# 09-multimodal-microcontroller-rf.net
KiCad netlist of a schematic drawn in Altium Designer
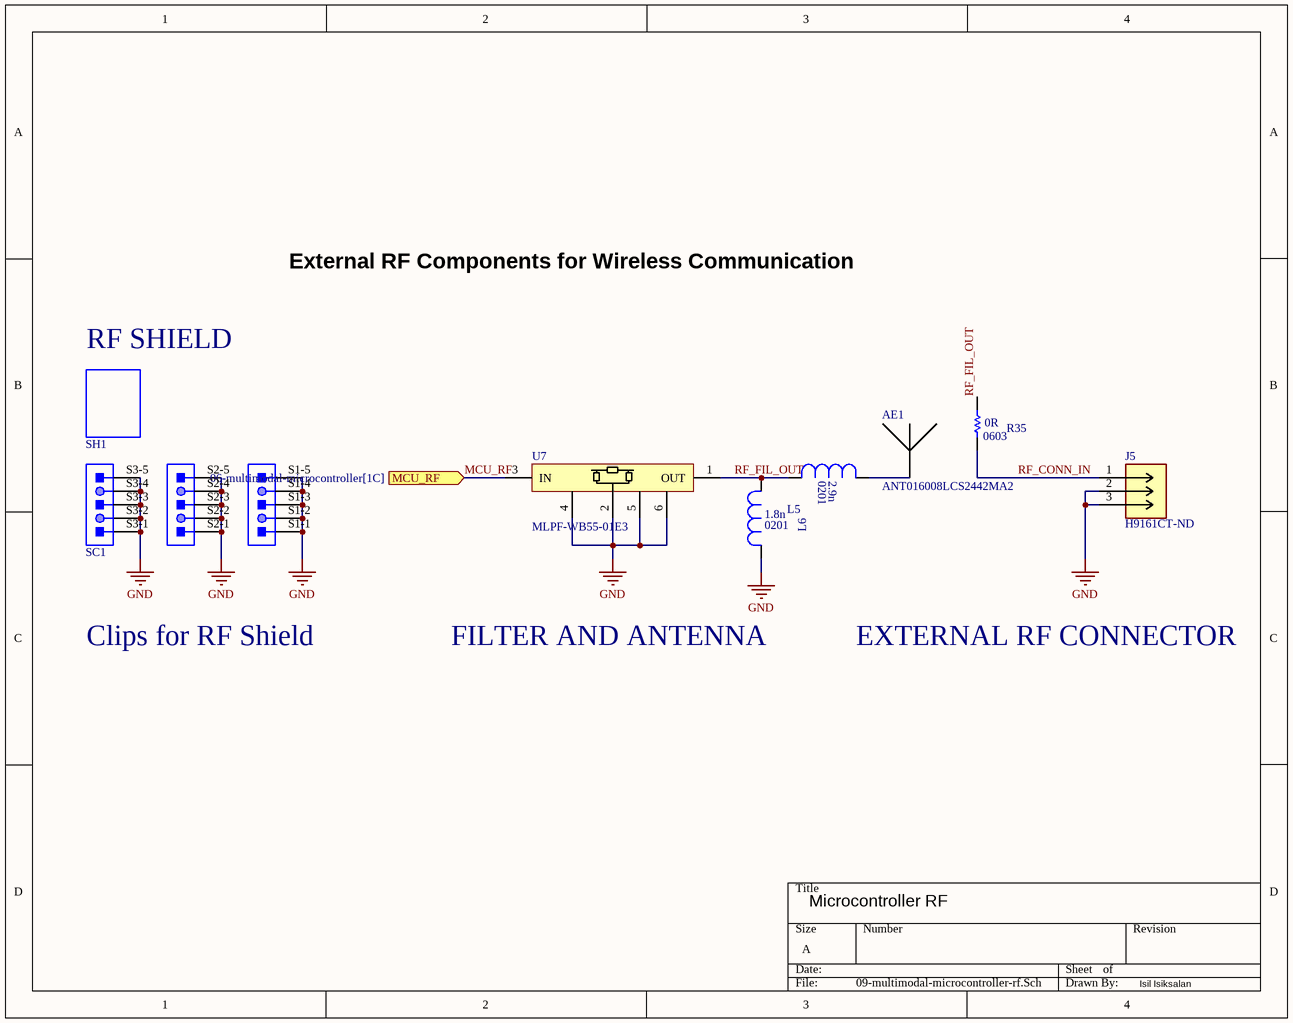
[diagram p0: 09-multimodal-microcontroller-rf.SchDoc]

(export (version "E")
  (design (tool "Eeschema 10.0.6"))
  (components
    (comp (ref "AE1")
      (value "ANT016008LCS2442MA2")
      (footprint "ANTENNA")
      (description "TDK - ANT016008LCS2442MA2 - Chip Antenna, ISM, 2.442 GHz, 50 Ohm, 1.6mm x 0.8mm x 0.4mm")
      (fields (field (name "MANUFACTURER") "TDK"))
      (libsource (lib "multimodal") (part "ANT016008LCS2442MA2"))
    )
    (comp (ref "J5")
      (value "U.FL-R-SMT(10)")
      (footprint "RF-CONNECTOR")
      (description "CONN U.FL RCPT STR 50 OHM SMD")
      (fields
        (field (name "MANUFACTURER") "Hirose")
        (field (name "SUPPLIER PART NUMBER 1") "H9161CT-ND")
        (field (name "COPYRIGHT") "Copyright (C) 2021 Ultra Librarian. All rights reserved.")
      )
      (libsource (lib "multimodal") (part "U.FL-R-SMT(10)"))
    )
    (comp (ref "L5")
      (value "MLG0603P1N8CT000")
      (footprint "INDTDK0201")
      (description "FIXED IND 1.8NH 700MA 100MOHM SM")
      (libsource (lib "multimodal") (part "MLG0603P1N8CT000"))
    )
    (comp (ref "L6")
      (value "MHQ0603P2N9ST000")
      (footprint "INDTDK0201")
      (description "FIXED IND 2.9NH 450MA 300MOHM SM")
      (libsource (lib "multimodal") (part "MHQ0603P2N9ST000"))
    )
    (comp (ref "R35")
      (value "RMCF0603ZT0R00")
      (footprint "RES-STACK-POLE-0603")
      (description "RES 0 OHM JUMPER 1/10W 0603")
      (libsource (lib "multimodal") (part "RMCF0603ZT0R00"))
    )
    (comp (ref "SC1")
      (value "S0951-46R")
      (footprint "RF-SHIELD+CLIP")
      (description "RFI SHIELD CLIP MINI TIN SMD")
      (libsource (lib "multimodal") (part "S0951-46R"))
    )
    (comp (ref "SH1")
      (value "MS190-10C")
      (description "RF SHLD COVER 0.563\"X0.764\" SNAP")
      (libsource (lib "multimodal") (part "MS190-10C"))
    )
    (comp (ref "U7")
      (value "MLPF-WB55-01E3")
      (footprint "Matched-Filter-2.4GHz")
      (description "2.4 GHz Matched filter companion chip for STM32WB55Cx and STM32WB55Rx")
      (fields (field (name "MANUFACTURER") "STMicroelectronics"))
      (libsource (lib "multimodal") (part "MLPF-WB55-01E3"))
    )
  )
  (nets
    (net (code "1") (name "/MCU_RF") (class "Default")
      (node (ref "U7") (pin "3") (pinfunction "IN_3") (pintype "passive"))
    )
    (net (code "2") (name "/RF_CONN_IN") (class "Default")
      (node (ref "J5") (pin "1") (pinfunction "1_1") (pintype "passive"))
      (node (ref "R35") (pin "1") (pinfunction "1_1") (pintype "passive"))
    )
    (net (code "3") (name "/RF_FIL_OUT") (class "Default")
      (node (ref "L5") (pin "1") (pinfunction "1_1") (pintype "passive"))
      (node (ref "L6") (pin "2") (pinfunction "2_2") (pintype "passive"))
      (node (ref "R35") (pin "2") (pinfunction "2_2") (pintype "passive"))
      (node (ref "U7") (pin "1") (pinfunction "OUT_1") (pintype "passive"))
    )
    (net (code "4") (name "GND") (class "Default")
      (node (ref "J5") (pin "2") (pinfunction "2_2") (pintype "passive"))
      (node (ref "J5") (pin "3") (pinfunction "3_3") (pintype "passive"))
      (node (ref "L5") (pin "2") (pinfunction "2_2") (pintype "passive"))
      (node (ref "SC1") (pin "S1-1") (pinfunction "S1-1_S1-1") (pintype "passive"))
      (node (ref "SC1") (pin "S1-2") (pinfunction "S1-2_S1-2") (pintype "passive"))
      (node (ref "SC1") (pin "S1-3") (pinfunction "S1-3_S1-3") (pintype "passive"))
      (node (ref "SC1") (pin "S1-4") (pinfunction "S1-4_S1-4") (pintype "passive"))
      (node (ref "SC1") (pin "S1-5") (pinfunction "S1-5_S1-5") (pintype "passive"))
      (node (ref "SC1") (pin "S2-1") (pinfunction "S2-1_S2-1") (pintype "passive"))
      (node (ref "SC1") (pin "S2-2") (pinfunction "S2-2_S2-2") (pintype "passive"))
      (node (ref "SC1") (pin "S2-3") (pinfunction "S2-3_S2-3") (pintype "passive"))
      (node (ref "SC1") (pin "S2-4") (pinfunction "S2-4_S2-4") (pintype "passive"))
      (node (ref "SC1") (pin "S2-5") (pinfunction "S2-5_S2-5") (pintype "passive"))
      (node (ref "SC1") (pin "S3-1") (pinfunction "S3-1_S3-1") (pintype "passive"))
      (node (ref "SC1") (pin "S3-2") (pinfunction "S3-2_S3-2") (pintype "passive"))
      (node (ref "SC1") (pin "S3-3") (pinfunction "S3-3_S3-3") (pintype "passive"))
      (node (ref "SC1") (pin "S3-4") (pinfunction "S3-4_S3-4") (pintype "passive"))
      (node (ref "SC1") (pin "S3-5") (pinfunction "S3-5_S3-5") (pintype "passive"))
      (node (ref "U7") (pin "2") (pinfunction "2_2") (pintype "passive"))
      (node (ref "U7") (pin "4") (pinfunction "4_4") (pintype "passive"))
      (node (ref "U7") (pin "5") (pinfunction "5_5") (pintype "passive"))
      (node (ref "U7") (pin "6") (pinfunction "6_6") (pintype "passive"))
    )
    (net (code "5") (name "Net-(AE1-Pad2)") (class "Default")
      (node (ref "AE1") (pin "2") (pinfunction "2_2") (pintype "passive"))
      (node (ref "L6") (pin "1") (pinfunction "1_1") (pintype "passive"))
    )
  )
)
